# ECE8873_sample.net
KiCad netlist of a schematic drawn in Altium Designer
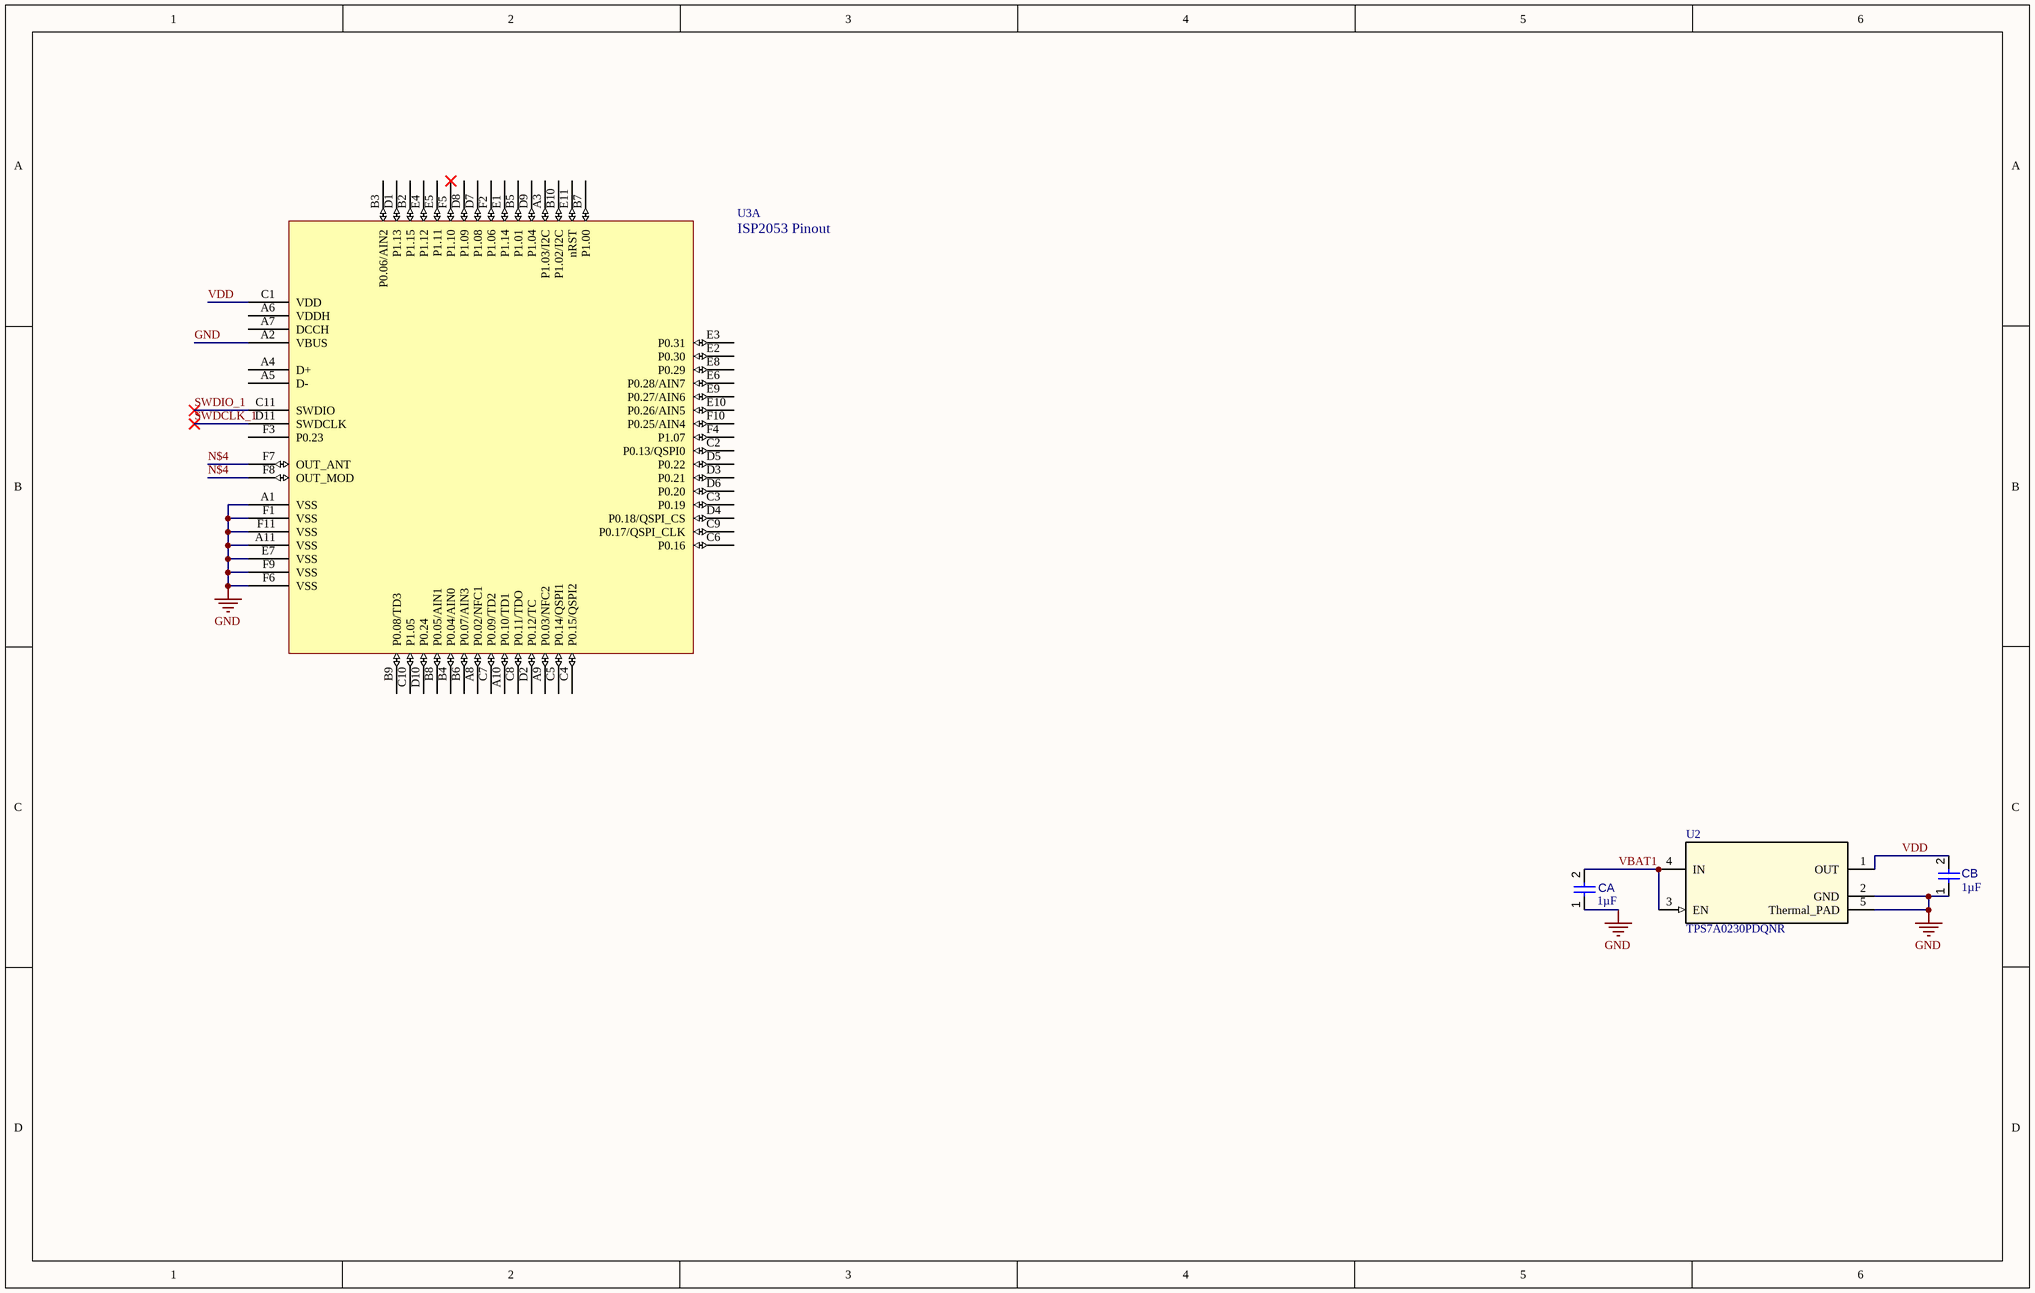
[diagram p0: ECE8873_sample.SchDoc]

(export (version "E")
  (design (tool "Eeschema 10.0.6"))
  (components
    (comp (ref "CA")
      (value "1µF")
      (footprint "CAPC1005X55X25LL05T10")
      (description "Chip Capacitor, 1 uF, +/- 10%, 6.3 V, 0402 (1005 Metric)")
      (fields (field (name "TOLERANCE") "10%") (field (name "Comment") "Capacitor 1 uF +/- 10% 6.3 V 0402"))
      (libsource (lib "Matthew Flavin") (part "CAP-NP-2"))
    )
    (comp (ref "CB")
      (value "1µF")
      (footprint "CAPC1005X55X25LL05T10")
      (description "Chip Capacitor, 1 uF, +/- 10%, 6.3 V, 0402 (1005 Metric)")
      (fields (field (name "TOLERANCE") "10%") (field (name "Comment") "Capacitor 1 uF +/- 10% 6.3 V 0402"))
      (libsource (lib "Matthew Flavin") (part "CAP-NP-2"))
    )
    (comp (ref "U2")
      (value "TPS7A0230PDQNR")
      (footprint "DQN0004A-MFG")
      (description "No Description Available")
      (libsource (lib "TPS7A0230PDQNR") (part "TPS7A0230PDQNR"))
    )
    (comp (ref "U3")
      (value "ISP1807")
      (footprint "ISP2053-AX")
      (description "ISP Smart Bluetooth Module")
      (fields (field (name "ALTIUM_UNNAMED_1") "ISP2053 Pinout"))
      (libsource (lib "ISPlibSch") (part "ISP2053_Pinout_New"))
    )
  )
  (nets
    (net (code "2") (name "/N$4") (class "Default")
      (node (ref "U3") (pin "F7") (pinfunction "OUT_ANT_F7") (pintype "bidirectional"))
      (node (ref "U3") (pin "F8") (pinfunction "OUT_MOD_F8") (pintype "bidirectional"))
    )
    (net (code "3") (name "/SWDCLK_1") (class "Default")
      (node (ref "U3") (pin "D11") (pinfunction "SWDCLK_D11") (pintype "passive+no_connect"))
    )
    (net (code "4") (name "/SWDIO_1") (class "Default")
      (node (ref "U3") (pin "C11") (pinfunction "SWDIO_C11") (pintype "passive+no_connect"))
    )
    (net (code "5") (name "/VBAT1") (class "Default")
      (node (ref "CA") (pin "2") (pinfunction "2_2") (pintype "passive"))
      (node (ref "U2") (pin "3") (pinfunction "EN_3") (pintype "input"))
      (node (ref "U2") (pin "4") (pinfunction "IN_4") (pintype "power_in"))
    )
    (net (code "6") (name "/VDD") (class "Default")
      (node (ref "CB") (pin "2") (pinfunction "2_2") (pintype "passive"))
      (node (ref "U2") (pin "1") (pinfunction "OUT_1") (pintype "power_in"))
      (node (ref "U3") (pin "C1") (pinfunction "VDD_C1") (pintype "power_in"))
    )
    (net (code "7") (name "GND") (class "Default")
      (node (ref "CA") (pin "1") (pinfunction "1_1") (pintype "passive"))
      (node (ref "CB") (pin "1") (pinfunction "1_1") (pintype "passive"))
      (node (ref "U2") (pin "2") (pinfunction "GND_2") (pintype "power_in"))
      (node (ref "U2") (pin "5") (pinfunction "Thermal_PAD_5") (pintype "passive"))
      (node (ref "U3") (pin "A1") (pinfunction "VSS_A1") (pintype "power_in"))
      (node (ref "U3") (pin "A11") (pinfunction "VSS_A11") (pintype "power_in"))
      (node (ref "U3") (pin "A2") (pinfunction "VBUS_A2") (pintype "power_in"))
      (node (ref "U3") (pin "E7") (pinfunction "VSS_E7") (pintype "power_in"))
      (node (ref "U3") (pin "F1") (pinfunction "VSS_F1") (pintype "power_in"))
      (node (ref "U3") (pin "F11") (pinfunction "VSS_F11") (pintype "power_in"))
      (node (ref "U3") (pin "F6") (pinfunction "VSS_F6") (pintype "power_in"))
      (node (ref "U3") (pin "F9") (pinfunction "VSS_F9") (pintype "power_in"))
    )
    (net (code "8") (name "unconnected-(U3A-D+-PadA4)") (class "Default")
      (node (ref "U3") (pin "A4") (pinfunction "D+_A4") (pintype "power_in"))
    )
    (net (code "9") (name "unconnected-(U3A-D--PadA5)") (class "Default")
      (node (ref "U3") (pin "A5") (pinfunction "D-_A5") (pintype "power_in"))
    )
    (net (code "10") (name "unconnected-(U3A-DCCH-PadA7)") (class "Default")
      (node (ref "U3") (pin "A7") (pinfunction "DCCH_A7") (pintype "power_in"))
    )
    (net (code "11") (name "unconnected-(U3A-P0.02{slash}NFC1-PadA8)") (class "Default")
      (node (ref "U3") (pin "A8") (pinfunction "P0.02/NFC1_A8") (pintype "bidirectional"))
    )
    (net (code "12") (name "unconnected-(U3A-P0.03{slash}NFC2-PadA9)") (class "Default")
      (node (ref "U3") (pin "A9") (pinfunction "P0.03/NFC2_A9") (pintype "bidirectional"))
    )
    (net (code "13") (name "unconnected-(U3A-P0.04{slash}AIN0-PadB4)") (class "Default")
      (node (ref "U3") (pin "B4") (pinfunction "P0.04/AIN0_B4") (pintype "bidirectional"))
    )
    (net (code "14") (name "unconnected-(U3A-P0.05{slash}AIN1-PadB8)") (class "Default")
      (node (ref "U3") (pin "B8") (pinfunction "P0.05/AIN1_B8") (pintype "bidirectional"))
    )
    (net (code "15") (name "unconnected-(U3A-P0.06{slash}AIN2-PadB3)") (class "Default")
      (node (ref "U3") (pin "B3") (pinfunction "P0.06/AIN2_B3") (pintype "bidirectional"))
    )
    (net (code "16") (name "unconnected-(U3A-P0.07{slash}AIN3-PadB6)") (class "Default")
      (node (ref "U3") (pin "B6") (pinfunction "P0.07/AIN3_B6") (pintype "bidirectional"))
    )
    (net (code "17") (name "unconnected-(U3A-P0.08{slash}TD3-PadB9)") (class "Default")
      (node (ref "U3") (pin "B9") (pinfunction "P0.08/TD3_B9") (pintype "bidirectional"))
    )
    (net (code "18") (name "unconnected-(U3A-P0.09{slash}TD2-PadC7)") (class "Default")
      (node (ref "U3") (pin "C7") (pinfunction "P0.09/TD2_C7") (pintype "bidirectional"))
    )
    (net (code "19") (name "unconnected-(U3A-P0.10{slash}TD1-PadA10)") (class "Default")
      (node (ref "U3") (pin "A10") (pinfunction "P0.10/TD1_A10") (pintype "bidirectional"))
    )
    (net (code "20") (name "unconnected-(U3A-P0.11{slash}TDO-PadC8)") (class "Default")
      (node (ref "U3") (pin "C8") (pinfunction "P0.11/TDO_C8") (pintype "bidirectional"))
    )
    (net (code "21") (name "unconnected-(U3A-P0.12{slash}TC-PadD2)") (class "Default")
      (node (ref "U3") (pin "D2") (pinfunction "P0.12/TC_D2") (pintype "bidirectional"))
    )
    (net (code "22") (name "unconnected-(U3A-P0.13{slash}QSPI0-PadC2)") (class "Default")
      (node (ref "U3") (pin "C2") (pinfunction "P0.13/QSPI0_C2") (pintype "bidirectional"))
    )
    (net (code "23") (name "unconnected-(U3A-P0.14{slash}QSPI1-PadC5)") (class "Default")
      (node (ref "U3") (pin "C5") (pinfunction "P0.14/QSPI1_C5") (pintype "bidirectional"))
    )
    (net (code "24") (name "unconnected-(U3A-P0.15{slash}QSPI2-PadC4)") (class "Default")
      (node (ref "U3") (pin "C4") (pinfunction "P0.15/QSPI2_C4") (pintype "bidirectional"))
    )
    (net (code "25") (name "unconnected-(U3A-P0.16-PadC6)") (class "Default")
      (node (ref "U3") (pin "C6") (pinfunction "P0.16_C6") (pintype "bidirectional"))
    )
    (net (code "26") (name "unconnected-(U3A-P0.17{slash}QSPI_CLK-PadC9)") (class "Default")
      (node (ref "U3") (pin "C9") (pinfunction "P0.17/QSPI_CLK_C9") (pintype "bidirectional"))
    )
    (net (code "27") (name "unconnected-(U3A-P0.18{slash}QSPI_CS-PadD4)") (class "Default")
      (node (ref "U3") (pin "D4") (pinfunction "P0.18/QSPI_CS_D4") (pintype "bidirectional"))
    )
    (net (code "28") (name "unconnected-(U3A-P0.19-PadC3)") (class "Default")
      (node (ref "U3") (pin "C3") (pinfunction "P0.19_C3") (pintype "bidirectional"))
    )
    (net (code "29") (name "unconnected-(U3A-P0.20-PadD6)") (class "Default")
      (node (ref "U3") (pin "D6") (pinfunction "P0.20_D6") (pintype "bidirectional"))
    )
    (net (code "30") (name "unconnected-(U3A-P0.21-PadD3)") (class "Default")
      (node (ref "U3") (pin "D3") (pinfunction "P0.21_D3") (pintype "bidirectional"))
    )
    (net (code "31") (name "unconnected-(U3A-P0.22-PadD5)") (class "Default")
      (node (ref "U3") (pin "D5") (pinfunction "P0.22_D5") (pintype "bidirectional"))
    )
    (net (code "32") (name "unconnected-(U3A-P0.23-PadF3)") (class "Default")
      (node (ref "U3") (pin "F3") (pinfunction "P0.23_F3") (pintype "power_in"))
    )
    (net (code "33") (name "unconnected-(U3A-P0.24-PadD10)") (class "Default")
      (node (ref "U3") (pin "D10") (pinfunction "P0.24_D10") (pintype "bidirectional"))
    )
    (net (code "34") (name "unconnected-(U3A-P0.25{slash}AIN4-PadF10)") (class "Default")
      (node (ref "U3") (pin "F10") (pinfunction "P0.25/AIN4_F10") (pintype "bidirectional"))
    )
    (net (code "35") (name "unconnected-(U3A-P0.26{slash}AIN5-PadE10)") (class "Default")
      (node (ref "U3") (pin "E10") (pinfunction "P0.26/AIN5_E10") (pintype "bidirectional"))
    )
    (net (code "36") (name "unconnected-(U3A-P0.27{slash}AIN6-PadE9)") (class "Default")
      (node (ref "U3") (pin "E9") (pinfunction "P0.27/AIN6_E9") (pintype "bidirectional"))
    )
    (net (code "37") (name "unconnected-(U3A-P0.28{slash}AIN7-PadE6)") (class "Default")
      (node (ref "U3") (pin "E6") (pinfunction "P0.28/AIN7_E6") (pintype "bidirectional"))
    )
    (net (code "38") (name "unconnected-(U3A-P0.29-PadE8)") (class "Default")
      (node (ref "U3") (pin "E8") (pinfunction "P0.29_E8") (pintype "bidirectional"))
    )
    (net (code "39") (name "unconnected-(U3A-P0.30-PadE2)") (class "Default")
      (node (ref "U3") (pin "E2") (pinfunction "P0.30_E2") (pintype "bidirectional"))
    )
    (net (code "40") (name "unconnected-(U3A-P0.31-PadE3)") (class "Default")
      (node (ref "U3") (pin "E3") (pinfunction "P0.31_E3") (pintype "bidirectional"))
    )
    (net (code "41") (name "unconnected-(U3A-P1.00-PadB7)") (class "Default")
      (node (ref "U3") (pin "B7") (pinfunction "P1.00_B7") (pintype "bidirectional"))
    )
    (net (code "42") (name "unconnected-(U3A-P1.01-PadB5)") (class "Default")
      (node (ref "U3") (pin "B5") (pinfunction "P1.01_B5") (pintype "bidirectional"))
    )
    (net (code "43") (name "unconnected-(U3A-P1.02{slash}I2C-PadB10)") (class "Default")
      (node (ref "U3") (pin "B10") (pinfunction "P1.02/I2C_B10") (pintype "bidirectional"))
    )
    (net (code "44") (name "unconnected-(U3A-P1.03{slash}I2C-PadA3)") (class "Default")
      (node (ref "U3") (pin "A3") (pinfunction "P1.03/I2C_A3") (pintype "bidirectional"))
    )
    (net (code "45") (name "unconnected-(U3A-P1.04-PadD9)") (class "Default")
      (node (ref "U3") (pin "D9") (pinfunction "P1.04_D9") (pintype "bidirectional"))
    )
    (net (code "46") (name "unconnected-(U3A-P1.05-PadC10)") (class "Default")
      (node (ref "U3") (pin "C10") (pinfunction "P1.05_C10") (pintype "bidirectional"))
    )
    (net (code "47") (name "unconnected-(U3A-P1.06-PadF2)") (class "Default")
      (node (ref "U3") (pin "F2") (pinfunction "P1.06_F2") (pintype "bidirectional"))
    )
    (net (code "48") (name "unconnected-(U3A-P1.07-PadF4)") (class "Default")
      (node (ref "U3") (pin "F4") (pinfunction "P1.07_F4") (pintype "bidirectional"))
    )
    (net (code "49") (name "unconnected-(U3A-P1.08-PadD7)") (class "Default")
      (node (ref "U3") (pin "D7") (pinfunction "P1.08_D7") (pintype "bidirectional"))
    )
    (net (code "50") (name "unconnected-(U3A-P1.09-PadD8)") (class "Default")
      (node (ref "U3") (pin "D8") (pinfunction "P1.09_D8") (pintype "bidirectional"))
    )
    (net (code "51") (name "unconnected-(U3A-P1.10-PadF5)") (class "Default")
      (node (ref "U3") (pin "F5") (pinfunction "P1.10_F5") (pintype "bidirectional+no_connect"))
    )
    (net (code "52") (name "unconnected-(U3A-P1.11-PadE5)") (class "Default")
      (node (ref "U3") (pin "E5") (pinfunction "P1.11_E5") (pintype "bidirectional"))
    )
    (net (code "53") (name "unconnected-(U3A-P1.12-PadE4)") (class "Default")
      (node (ref "U3") (pin "E4") (pinfunction "P1.12_E4") (pintype "bidirectional"))
    )
    (net (code "54") (name "unconnected-(U3A-P1.13-PadD1)") (class "Default")
      (node (ref "U3") (pin "D1") (pinfunction "P1.13_D1") (pintype "bidirectional"))
    )
    (net (code "55") (name "unconnected-(U3A-P1.14-PadE1)") (class "Default")
      (node (ref "U3") (pin "E1") (pinfunction "P1.14_E1") (pintype "bidirectional"))
    )
    (net (code "56") (name "unconnected-(U3A-P1.15-PadB2)") (class "Default")
      (node (ref "U3") (pin "B2") (pinfunction "P1.15_B2") (pintype "bidirectional"))
    )
    (net (code "57") (name "unconnected-(U3A-VDDH-PadA6)") (class "Default")
      (node (ref "U3") (pin "A6") (pinfunction "VDDH_A6") (pintype "power_in"))
    )
    (net (code "58") (name "unconnected-(U3A-nRST-PadE11)") (class "Default")
      (node (ref "U3") (pin "E11") (pinfunction "nRST_E11") (pintype "bidirectional"))
    )
  )
)
